# keyboard.net
KiCad netlist of a schematic drawn in EAGLE
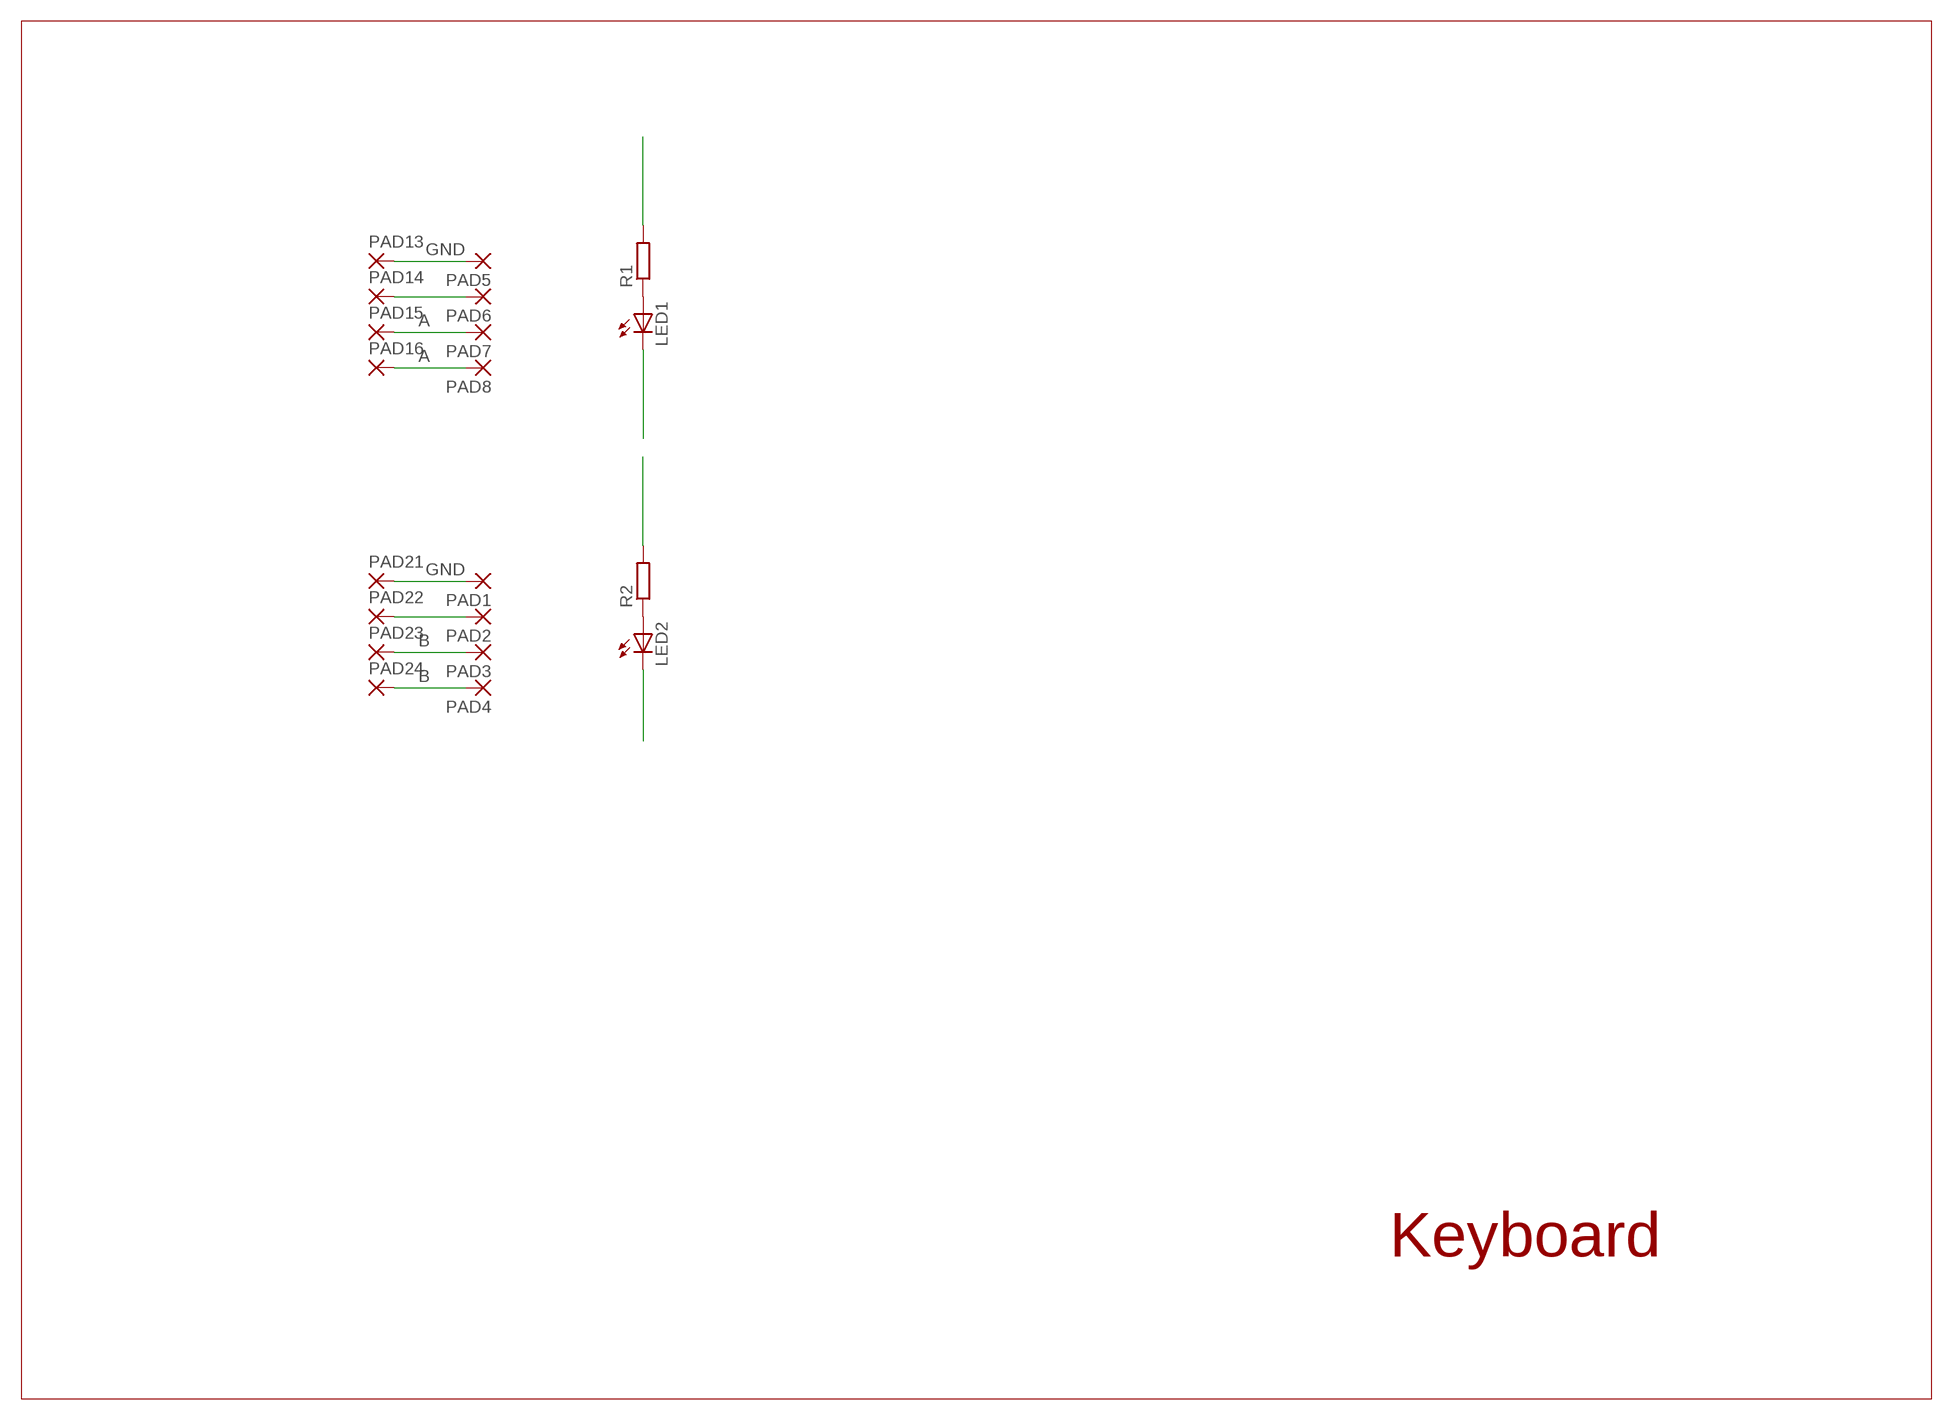
[diagram p0: schematic, sheet 1]

(export (version "E")
  (design (tool "Eeschema 10.0.6"))
  (components
    (comp (ref "LED1")
      (value "LEDCHIP-LED0805")
      (footprint "eagle-import:CHIP-LED0805")
      (libsource (lib "eagle-import") (part "LEDCHIP-LED0805"))
    )
    (comp (ref "LED2")
      (value "LEDCHIP-LED0805")
      (footprint "eagle-import:CHIP-LED0805")
      (libsource (lib "eagle-import") (part "LEDCHIP-LED0805"))
    )
    (comp (ref "PAD1")
      (value "WIREPAD1,6/0,8")
      (footprint "eagle-import:1,6_0,8")
      (libsource (lib "eagle-import") (part "WIREPAD1,6/0,8"))
    )
    (comp (ref "PAD2")
      (value "WIREPAD1,6/0,8")
      (footprint "eagle-import:1,6_0,8")
      (libsource (lib "eagle-import") (part "WIREPAD1,6/0,8"))
    )
    (comp (ref "PAD3")
      (value "WIREPAD1,6/0,8")
      (footprint "eagle-import:1,6_0,8")
      (libsource (lib "eagle-import") (part "WIREPAD1,6/0,8"))
    )
    (comp (ref "PAD4")
      (value "WIREPAD1,6/0,8")
      (footprint "eagle-import:1,6_0,8")
      (libsource (lib "eagle-import") (part "WIREPAD1,6/0,8"))
    )
    (comp (ref "PAD5")
      (value "WIREPAD1,6/0,8")
      (footprint "eagle-import:1,6_0,8")
      (libsource (lib "eagle-import") (part "WIREPAD1,6/0,8"))
    )
    (comp (ref "PAD6")
      (value "WIREPAD1,6/0,8")
      (footprint "eagle-import:1,6_0,8")
      (libsource (lib "eagle-import") (part "WIREPAD1,6/0,8"))
    )
    (comp (ref "PAD7")
      (value "WIREPAD1,6/0,8")
      (footprint "eagle-import:1,6_0,8")
      (libsource (lib "eagle-import") (part "WIREPAD1,6/0,8"))
    )
    (comp (ref "PAD8")
      (value "WIREPAD1,6/0,8")
      (footprint "eagle-import:1,6_0,8")
      (libsource (lib "eagle-import") (part "WIREPAD1,6/0,8"))
    )
    (comp (ref "PAD13")
      (value "WIREPAD1,6/0,8")
      (footprint "eagle-import:1,6_0,8")
      (libsource (lib "eagle-import") (part "WIREPAD1,6/0,8"))
    )
    (comp (ref "PAD14")
      (value "WIREPAD1,6/0,8")
      (footprint "eagle-import:1,6_0,8")
      (libsource (lib "eagle-import") (part "WIREPAD1,6/0,8"))
    )
    (comp (ref "PAD15")
      (value "WIREPAD1,6/0,8")
      (footprint "eagle-import:1,6_0,8")
      (libsource (lib "eagle-import") (part "WIREPAD1,6/0,8"))
    )
    (comp (ref "PAD16")
      (value "WIREPAD1,6/0,8")
      (footprint "eagle-import:1,6_0,8")
      (libsource (lib "eagle-import") (part "WIREPAD1,6/0,8"))
    )
    (comp (ref "PAD21")
      (value "WIREPAD1,6/0,8")
      (footprint "eagle-import:1,6_0,8")
      (libsource (lib "eagle-import") (part "WIREPAD1,6/0,8"))
    )
    (comp (ref "PAD22")
      (value "WIREPAD1,6/0,8")
      (footprint "eagle-import:1,6_0,8")
      (libsource (lib "eagle-import") (part "WIREPAD1,6/0,8"))
    )
    (comp (ref "PAD23")
      (value "WIREPAD1,6/0,8")
      (footprint "eagle-import:1,6_0,8")
      (libsource (lib "eagle-import") (part "WIREPAD1,6/0,8"))
    )
    (comp (ref "PAD24")
      (value "WIREPAD1,6/0,8")
      (footprint "eagle-import:1,6_0,8")
      (libsource (lib "eagle-import") (part "WIREPAD1,6/0,8"))
    )
    (comp (ref "R1")
      (value "R-EU_R0805")
      (footprint "eagle-import:R0805")
      (libsource (lib "eagle-import") (part "R-EU_R0805"))
    )
    (comp (ref "R2")
      (value "R-EU_R0805")
      (footprint "eagle-import:R0805")
      (libsource (lib "eagle-import") (part "R-EU_R0805"))
    )
  )
  (nets
    (net (code "1") (name "/A") (class "Default")
      (node (ref "PAD15") (pin "1") (pinfunction "P_1") (pintype "passive"))
      (node (ref "PAD16") (pin "1") (pinfunction "P_1") (pintype "passive"))
      (node (ref "PAD7") (pin "1") (pinfunction "P_1") (pintype "passive"))
      (node (ref "PAD8") (pin "1") (pinfunction "P_1") (pintype "passive"))
      (node (ref "R1") (pin "2") (pinfunction "2_2") (pintype "passive"))
    )
    (net (code "2") (name "/B") (class "Default")
      (node (ref "PAD23") (pin "1") (pinfunction "P_1") (pintype "passive"))
      (node (ref "PAD24") (pin "1") (pinfunction "P_1") (pintype "passive"))
      (node (ref "PAD3") (pin "1") (pinfunction "P_1") (pintype "passive"))
      (node (ref "PAD4") (pin "1") (pinfunction "P_1") (pintype "passive"))
      (node (ref "R2") (pin "2") (pinfunction "2_2") (pintype "passive"))
    )
    (net (code "3") (name "/GND") (class "Default")
      (node (ref "LED1") (pin "C") (pinfunction "C_C") (pintype "passive"))
      (node (ref "LED2") (pin "C") (pinfunction "C_C") (pintype "passive"))
      (node (ref "PAD1") (pin "1") (pinfunction "P_1") (pintype "passive"))
      (node (ref "PAD13") (pin "1") (pinfunction "P_1") (pintype "passive"))
      (node (ref "PAD14") (pin "1") (pinfunction "P_1") (pintype "passive"))
      (node (ref "PAD2") (pin "1") (pinfunction "P_1") (pintype "passive"))
      (node (ref "PAD21") (pin "1") (pinfunction "P_1") (pintype "passive"))
      (node (ref "PAD22") (pin "1") (pinfunction "P_1") (pintype "passive"))
      (node (ref "PAD5") (pin "1") (pinfunction "P_1") (pintype "passive"))
      (node (ref "PAD6") (pin "1") (pinfunction "P_1") (pintype "passive"))
    )
    (net (code "4") (name "Net-(LED1-PadA)") (class "Default")
      (node (ref "LED1") (pin "A") (pinfunction "A_A") (pintype "passive"))
      (node (ref "R1") (pin "1") (pinfunction "1_1") (pintype "passive"))
    )
    (net (code "5") (name "Net-(LED2-PadA)") (class "Default")
      (node (ref "LED2") (pin "A") (pinfunction "A_A") (pintype "passive"))
      (node (ref "R2") (pin "1") (pinfunction "1_1") (pintype "passive"))
    )
  )
)
